# M868tqfp.net
KiCad netlist of a schematic drawn in EAGLE
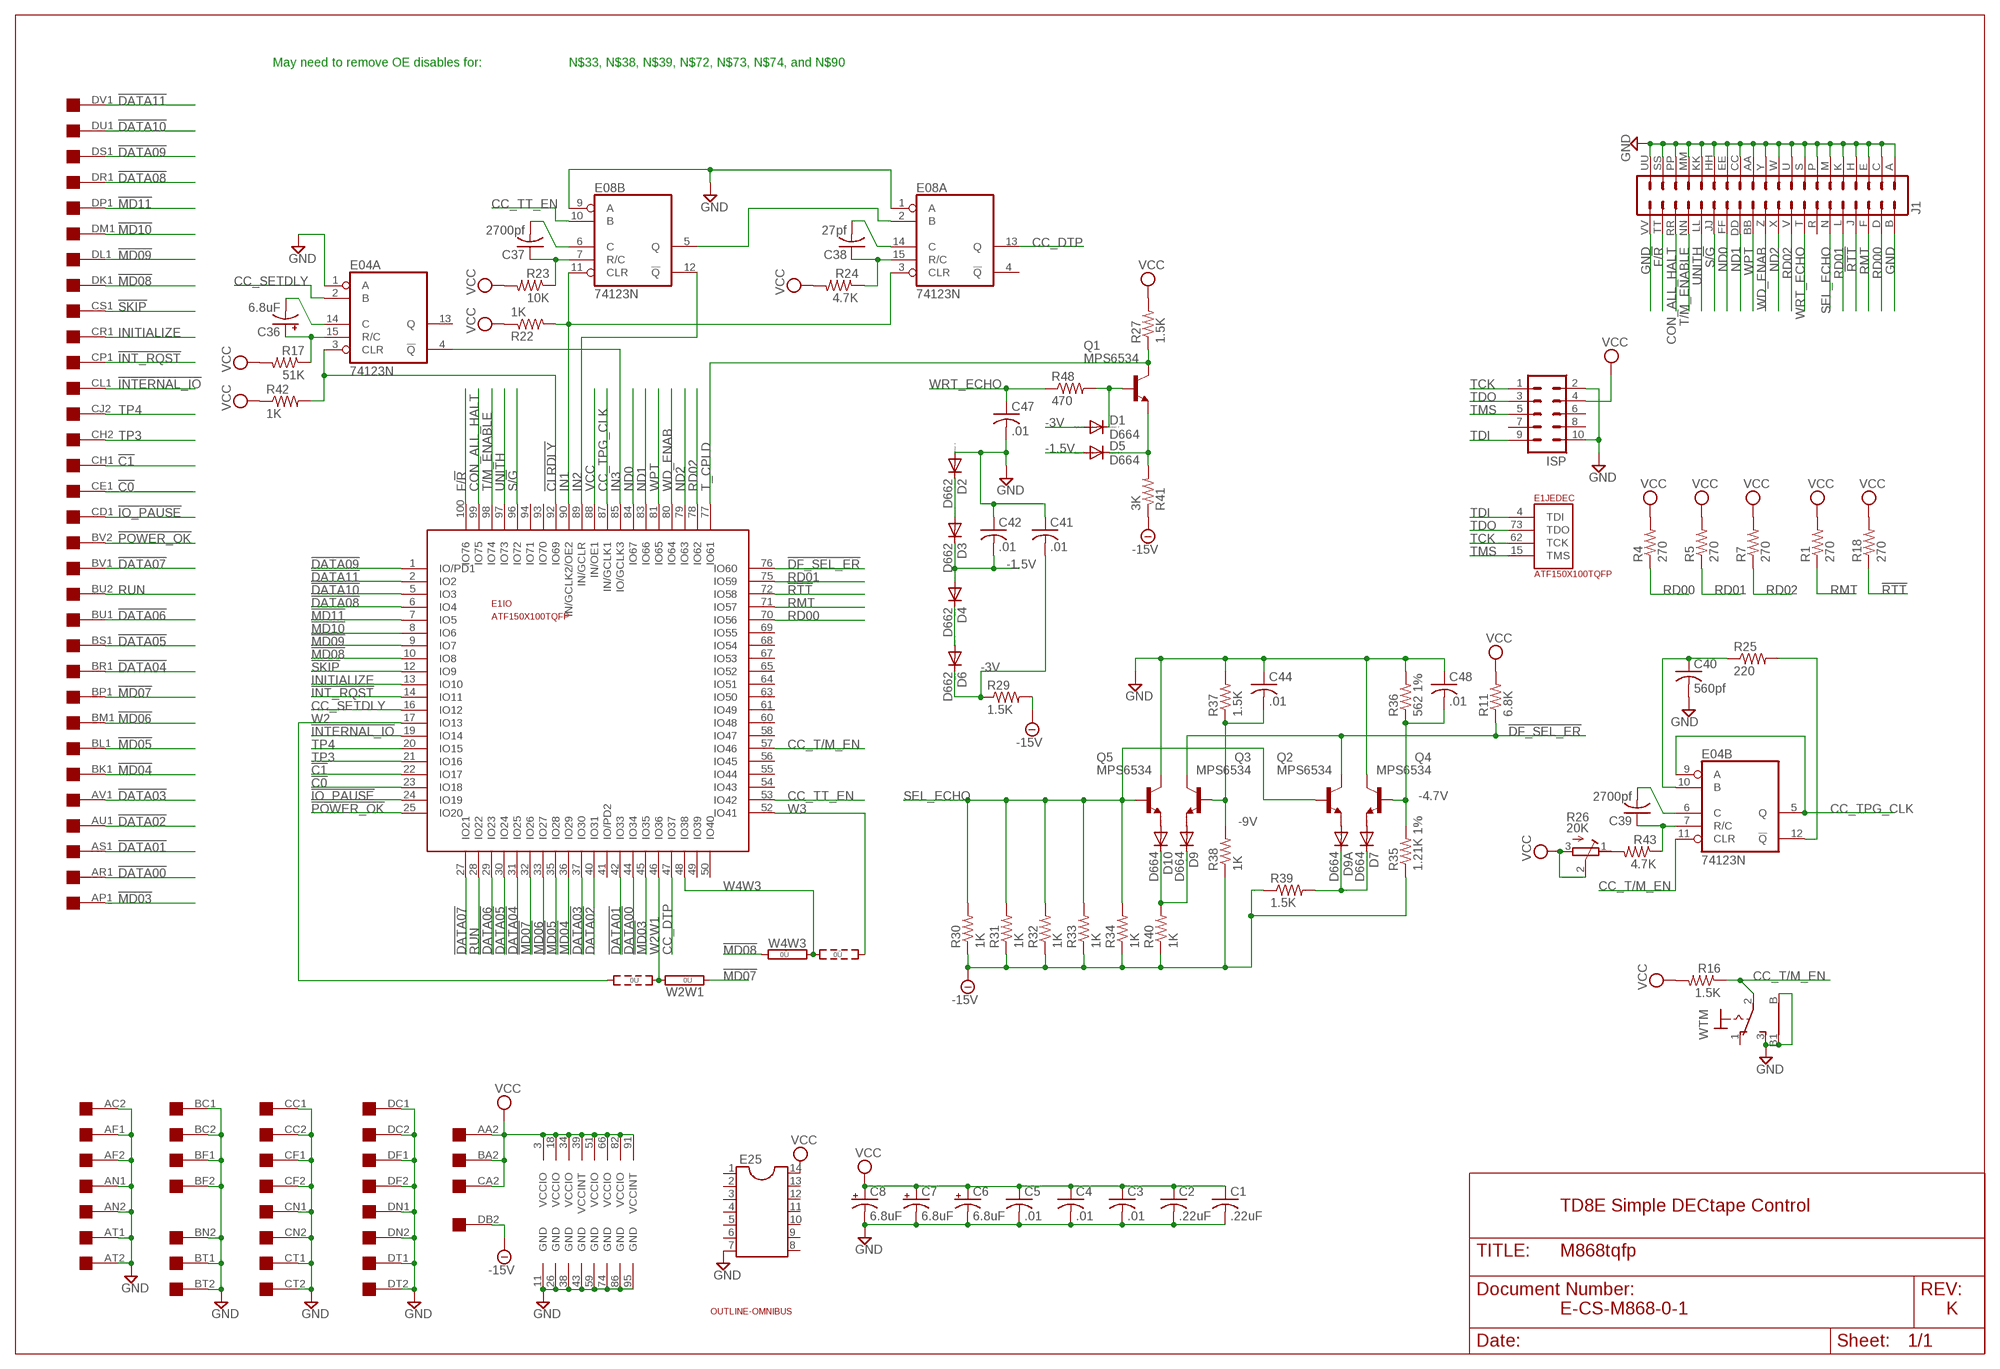
[diagram p0: schematic, sheet 1]

(export (version "E")
  (design (tool "Eeschema 10.0.6"))
  (components
    (comp (ref "C1")
      (value ".22uF")
      (footprint "eagle-import:C050-025X075")
      (libsource (lib "eagle-import") (part "C-US050-025X075"))
    )
    (comp (ref "C2")
      (value ".22uF")
      (footprint "eagle-import:C050-025X075")
      (libsource (lib "eagle-import") (part "C-US050-025X075"))
    )
    (comp (ref "C3")
      (value ".01")
      (footprint "eagle-import:C050-025X075")
      (libsource (lib "eagle-import") (part "C-US050-025X075"))
    )
    (comp (ref "C4")
      (value ".01")
      (footprint "eagle-import:C050-025X075")
      (libsource (lib "eagle-import") (part "C-US050-025X075"))
    )
    (comp (ref "C5")
      (value ".01")
      (footprint "eagle-import:C050-025X075")
      (libsource (lib "eagle-import") (part "C-US050-025X075"))
    )
    (comp (ref "C6")
      (value "6.8uF")
      (footprint "eagle-import:E12-8")
      (libsource (lib "eagle-import") (part "CPOL-USE20-8AXIAL"))
    )
    (comp (ref "C7")
      (value "6.8uF")
      (footprint "eagle-import:E12-8")
      (libsource (lib "eagle-import") (part "CPOL-USE20-8AXIAL"))
    )
    (comp (ref "C8")
      (value "6.8uF")
      (footprint "eagle-import:E12-8")
      (libsource (lib "eagle-import") (part "CPOL-USE20-8AXIAL"))
    )
    (comp (ref "C36")
      (value "6.8uF")
      (footprint "eagle-import:E12-8")
      (libsource (lib "eagle-import") (part "CPOL-USE20-8AXIAL"))
    )
    (comp (ref "C37")
      (value "2700pf")
      (footprint "eagle-import:C102-043X133")
      (libsource (lib "eagle-import") (part "C-US102-043X133"))
    )
    (comp (ref "C38")
      (value "27pf")
      (footprint "eagle-import:C050-025X075")
      (libsource (lib "eagle-import") (part "C-US050-025X075"))
    )
    (comp (ref "C39")
      (value "2700pf")
      (footprint "eagle-import:C102-043X133")
      (libsource (lib "eagle-import") (part "C-US102-043X133"))
    )
    (comp (ref "C40")
      (value "560pf")
      (footprint "eagle-import:C075-032X103")
      (libsource (lib "eagle-import") (part "C-US075-032X103"))
    )
    (comp (ref "C41")
      (value ".01")
      (footprint "eagle-import:C050-025X075")
      (libsource (lib "eagle-import") (part "C-US050-025X075"))
    )
    (comp (ref "C42")
      (value ".01")
      (footprint "eagle-import:C050-025X075")
      (libsource (lib "eagle-import") (part "C-US050-025X075"))
    )
    (comp (ref "C44")
      (value ".01")
      (footprint "eagle-import:C050-025X075")
      (libsource (lib "eagle-import") (part "C-US050-025X075"))
    )
    (comp (ref "C47")
      (value ".01")
      (footprint "eagle-import:C050-025X075")
      (libsource (lib "eagle-import") (part "C-US050-025X075"))
    )
    (comp (ref "C48")
      (value ".01")
      (footprint "eagle-import:C050-025X075")
      (libsource (lib "eagle-import") (part "C-US050-025X075"))
    )
    (comp (ref "D1")
      (value "D664")
      (footprint "eagle-import:DO35-10")
      (libsource (lib "eagle-import") (part "1N4148DO35-10"))
    )
    (comp (ref "D2")
      (value "D662")
      (footprint "eagle-import:DO35-10")
      (libsource (lib "eagle-import") (part "1N4148DO35-10"))
    )
    (comp (ref "D3")
      (value "D662")
      (footprint "eagle-import:DO35-10")
      (libsource (lib "eagle-import") (part "1N4148DO35-10"))
    )
    (comp (ref "D4")
      (value "D662")
      (footprint "eagle-import:DO35-10")
      (libsource (lib "eagle-import") (part "1N4148DO35-10"))
    )
    (comp (ref "D5")
      (value "D664")
      (footprint "eagle-import:DO35-10")
      (libsource (lib "eagle-import") (part "1N4148DO35-10"))
    )
    (comp (ref "D6")
      (value "D662")
      (footprint "eagle-import:DO35-10")
      (libsource (lib "eagle-import") (part "1N4148DO35-10"))
    )
    (comp (ref "D7")
      (value "D664")
      (footprint "eagle-import:DO35-10")
      (libsource (lib "eagle-import") (part "1N4148DO35-10"))
    )
    (comp (ref "D9")
      (value "D664")
      (footprint "eagle-import:DO35-10")
      (libsource (lib "eagle-import") (part "1N4148DO35-10"))
    )
    (comp (ref "D9A")
      (value "D664")
      (footprint "eagle-import:DO35-10")
      (libsource (lib "eagle-import") (part "1N4148DO35-10"))
    )
    (comp (ref "D10")
      (value "D664")
      (footprint "eagle-import:DO35-10")
      (libsource (lib "eagle-import") (part "1N4148DO35-10"))
    )
    (comp (ref "E1")
      (value "ATF150X100TQFP")
      (footprint "eagle-import:TQFP-100")
      (libsource (lib "eagle-import") (part "ATF150X100TQFP"))
    )
    (comp (ref "E04")
      (value "74123N")
      (footprint "eagle-import:DIL16")
      (libsource (lib "eagle-import") (part "74123N"))
    )
    (comp (ref "E08")
      (value "74123N")
      (footprint "eagle-import:DIL16")
      (libsource (lib "eagle-import") (part "74123N"))
    )
    (comp (ref "E25")
      (value "DIL14")
      (footprint "eagle-import:DIL14")
      (libsource (lib "eagle-import") (part "DIL14"))
    )
    (comp (ref "EDGE$3")
      (value "QUAD")
      (footprint "eagle-import:EDGE-CON8")
      (libsource (lib "eagle-import") (part "QUAD"))
    )
    (comp (ref "ISP")
      (value "ML10")
      (footprint "eagle-import:ML10")
      (libsource (lib "eagle-import") (part "ML10"))
    )
    (comp (ref "J1")
      (value "DEC40PINH")
      (footprint "eagle-import:DEC40PINH")
      (libsource (lib "eagle-import") (part "DEC40PINH"))
    )
    (comp (ref "Q1")
      (value "MPS6534")
      (footprint "eagle-import:TO5")
      (libsource (lib "eagle-import") (part "2N2219"))
    )
    (comp (ref "Q2")
      (value "MPS6534")
      (footprint "eagle-import:TO5")
      (libsource (lib "eagle-import") (part "2N2219"))
    )
    (comp (ref "Q3")
      (value "MPS6534")
      (footprint "eagle-import:TO5")
      (libsource (lib "eagle-import") (part "2N2219"))
    )
    (comp (ref "Q4")
      (value "MPS6534")
      (footprint "eagle-import:TO5")
      (libsource (lib "eagle-import") (part "2N2219"))
    )
    (comp (ref "Q5")
      (value "MPS6534")
      (footprint "eagle-import:TO5")
      (libsource (lib "eagle-import") (part "2N2219"))
    )
    (comp (ref "R1")
      (value "270")
      (footprint "eagle-import:0207_10")
      (libsource (lib "eagle-import") (part "R-US_0207/10"))
    )
    (comp (ref "R4")
      (value "270")
      (footprint "eagle-import:0207_10")
      (libsource (lib "eagle-import") (part "R-US_0207/10"))
    )
    (comp (ref "R5")
      (value "270")
      (footprint "eagle-import:0207_10")
      (libsource (lib "eagle-import") (part "R-US_0207/10"))
    )
    (comp (ref "R7")
      (value "270")
      (footprint "eagle-import:0207_10")
      (libsource (lib "eagle-import") (part "R-US_0207/10"))
    )
    (comp (ref "R11")
      (value "6.8K")
      (footprint "eagle-import:0207_10")
      (libsource (lib "eagle-import") (part "R-US_0207/10"))
    )
    (comp (ref "R16")
      (value "1.5K")
      (footprint "eagle-import:0207_10")
      (libsource (lib "eagle-import") (part "R-US_0207/10"))
    )
    (comp (ref "R17")
      (value "51K")
      (footprint "eagle-import:0207_10")
      (libsource (lib "eagle-import") (part "R-US_0207/10"))
    )
    (comp (ref "R18")
      (value "270")
      (footprint "eagle-import:0207_10")
      (libsource (lib "eagle-import") (part "R-US_0207/10"))
    )
    (comp (ref "R22")
      (value "1K")
      (footprint "eagle-import:0207_10")
      (libsource (lib "eagle-import") (part "R-US_0207/10"))
    )
    (comp (ref "R23")
      (value "10K")
      (footprint "eagle-import:0207_10")
      (libsource (lib "eagle-import") (part "R-US_0207/10"))
    )
    (comp (ref "R24")
      (value "4.7K")
      (footprint "eagle-import:0207_10")
      (libsource (lib "eagle-import") (part "R-US_0207/10"))
    )
    (comp (ref "R25")
      (value "220")
      (footprint "eagle-import:0207_10")
      (libsource (lib "eagle-import") (part "R-US_0207/10"))
    )
    (comp (ref "R26")
      (value "20K")
      (footprint "eagle-import:3006Y")
      (libsource (lib "eagle-import") (part "275P"))
    )
    (comp (ref "R27")
      (value "1.5K")
      (footprint "eagle-import:0207_10")
      (libsource (lib "eagle-import") (part "R-US_0207/10"))
    )
    (comp (ref "R29")
      (value "1.5K")
      (footprint "eagle-import:0207_10")
      (libsource (lib "eagle-import") (part "R-US_0207/10"))
    )
    (comp (ref "R30")
      (value "1K")
      (footprint "eagle-import:0207_10")
      (libsource (lib "eagle-import") (part "R-US_0207/10"))
    )
    (comp (ref "R31")
      (value "1K")
      (footprint "eagle-import:0207_10")
      (libsource (lib "eagle-import") (part "R-US_0207/10"))
    )
    (comp (ref "R32")
      (value "1K")
      (footprint "eagle-import:0207_10")
      (libsource (lib "eagle-import") (part "R-US_0207/10"))
    )
    (comp (ref "R33")
      (value "1K")
      (footprint "eagle-import:0207_10")
      (libsource (lib "eagle-import") (part "R-US_0207/10"))
    )
    (comp (ref "R34")
      (value "1K")
      (footprint "eagle-import:0207_10")
      (libsource (lib "eagle-import") (part "R-US_0207/10"))
    )
    (comp (ref "R35")
      (value "1.21K 1%")
      (footprint "eagle-import:0207_15")
      (libsource (lib "eagle-import") (part "R-US_0207/15"))
    )
    (comp (ref "R36")
      (value "562 1%")
      (footprint "eagle-import:0207_15")
      (libsource (lib "eagle-import") (part "R-US_0207/15"))
    )
    (comp (ref "R37")
      (value "1.5K")
      (footprint "eagle-import:0207_10")
      (libsource (lib "eagle-import") (part "R-US_0207/10"))
    )
    (comp (ref "R38")
      (value "1K")
      (footprint "eagle-import:0207_10")
      (libsource (lib "eagle-import") (part "R-US_0207/10"))
    )
    (comp (ref "R39")
      (value "1.5K")
      (footprint "eagle-import:0207_10")
      (libsource (lib "eagle-import") (part "R-US_0207/10"))
    )
    (comp (ref "R40")
      (value "1K")
      (footprint "eagle-import:0207_10")
      (libsource (lib "eagle-import") (part "R-US_0207/10"))
    )
    (comp (ref "R41")
      (value "3K")
      (footprint "eagle-import:0207_10")
      (libsource (lib "eagle-import") (part "R-US_0207/10"))
    )
    (comp (ref "R42")
      (value "1K")
      (footprint "eagle-import:0207_10")
      (libsource (lib "eagle-import") (part "R-US_0207/10"))
    )
    (comp (ref "R43")
      (value "4.7K")
      (footprint "eagle-import:0207_10")
      (libsource (lib "eagle-import") (part "R-US_0207/10"))
    )
    (comp (ref "R48")
      (value "470")
      (footprint "eagle-import:0207_10")
      (libsource (lib "eagle-import") (part "R-US_0207/10"))
    )
    (comp (ref "U$1")
      (value "OUTLINE-OMNIBUS")
      (footprint "eagle-import:OMNIBUS")
      (libsource (lib "eagle-import") (part "OUTLINE-OMNIBUS"))
    )
    (comp (ref "W2W1")
      (value "0R2")
      (footprint "eagle-import:0R2_10")
      (libsource (lib "eagle-import") (part "0R2"))
    )
    (comp (ref "W4W3")
      (value "0R2")
      (footprint "eagle-import:0R2_10")
      (libsource (lib "eagle-import") (part "0R2"))
    )
    (comp (ref "WTM")
      (value "9070-1W")
      (footprint "eagle-import:9070-1W")
      (libsource (lib "eagle-import") (part "9070-1W"))
    )
  )
  (nets
    (net (code "1") (name "-15V") (class "Default")
      (node (ref "EDGE$3") (pin "DB2") (pinfunction "1_DB2") (pintype "bidirectional"))
      (node (ref "R29") (pin "2") (pinfunction "2_2") (pintype "passive"))
      (node (ref "R30") (pin "1") (pinfunction "1_1") (pintype "passive"))
      (node (ref "R31") (pin "1") (pinfunction "1_1") (pintype "passive"))
      (node (ref "R32") (pin "1") (pinfunction "1_1") (pintype "passive"))
      (node (ref "R33") (pin "1") (pinfunction "1_1") (pintype "passive"))
      (node (ref "R34") (pin "1") (pinfunction "1_1") (pintype "passive"))
      (node (ref "R35") (pin "1") (pinfunction "1_1") (pintype "passive"))
      (node (ref "R38") (pin "1") (pinfunction "1_1") (pintype "passive"))
      (node (ref "R39") (pin "1") (pinfunction "1_1") (pintype "passive"))
      (node (ref "R40") (pin "1") (pinfunction "1_1") (pintype "passive"))
      (node (ref "R41") (pin "1") (pinfunction "1_1") (pintype "passive"))
    )
    (net (code "2") (name "/-1.5V") (class "Default")
      (node (ref "C42") (pin "2") (pinfunction "2_2") (pintype "passive"))
      (node (ref "D3") (pin "C") (pinfunction "C_C") (pintype "passive"))
      (node (ref "D4") (pin "A") (pinfunction "A_A") (pintype "passive"))
      (node (ref "D5") (pin "A") (pinfunction "A_A") (pintype "passive"))
    )
    (net (code "3") (name "/-3V") (class "Default")
      (node (ref "C41") (pin "2") (pinfunction "2_2") (pintype "passive"))
      (node (ref "D1") (pin "A") (pinfunction "A_A") (pintype "passive"))
      (node (ref "D6") (pin "C") (pinfunction "C_C") (pintype "passive"))
      (node (ref "R29") (pin "1") (pinfunction "1_1") (pintype "passive"))
    )
    (net (code "4") (name "/-4.7V") (class "Default")
      (node (ref "C48") (pin "2") (pinfunction "2_2") (pintype "passive"))
      (node (ref "Q4") (pin "2") (pinfunction "B_2") (pintype "passive"))
      (node (ref "R35") (pin "2") (pinfunction "2_2") (pintype "passive"))
      (node (ref "R36") (pin "1") (pinfunction "1_1") (pintype "passive"))
    )
    (net (code "5") (name "/-9V") (class "Default")
      (node (ref "C44") (pin "2") (pinfunction "2_2") (pintype "passive"))
      (node (ref "Q3") (pin "2") (pinfunction "B_2") (pintype "passive"))
      (node (ref "R37") (pin "1") (pinfunction "1_1") (pintype "passive"))
      (node (ref "R38") (pin "2") (pinfunction "2_2") (pintype "passive"))
    )
    (net (code "6") (name "/CC_DTP") (class "Default")
      (node (ref "E08") (pin "13") (pinfunction "Q_13") (pintype "output"))
      (node (ref "E1") (pin "47") (pinfunction "IO37_47") (pintype "bidirectional"))
    )
    (net (code "7") (name "/CC_SETDLY") (class "Default")
      (node (ref "E04") (pin "2") (pinfunction "B_2") (pintype "input"))
      (node (ref "E1") (pin "16") (pinfunction "IO12_16") (pintype "bidirectional"))
    )
    (net (code "8") (name "/CC_TPG_CLK") (class "Default")
      (node (ref "E04") (pin "5") (pinfunction "Q_5") (pintype "output"))
      (node (ref "E04") (pin "9") (pinfunction "A_9") (pintype "input"))
      (node (ref "E1") (pin "87") (pinfunction "IN/GCLK1_87") (pintype "input"))
    )
    (net (code "9") (name "/CC_TT_EN") (class "Default")
      (node (ref "E08") (pin "10") (pinfunction "B_10") (pintype "input"))
      (node (ref "E1") (pin "53") (pinfunction "IO42_53") (pintype "bidirectional"))
    )
    (net (code "10") (name "/CC_T{slash}M_EN") (class "Default")
      (node (ref "E04") (pin "11") (pinfunction "CLR_11") (pintype "input"))
      (node (ref "E1") (pin "57") (pinfunction "IO46_57") (pintype "bidirectional"))
      (node (ref "R16") (pin "1") (pinfunction "1_1") (pintype "passive"))
      (node (ref "WTM") (pin "2") (pinfunction "P_2") (pintype "passive"))
    )
    (net (code "11") (name "/CON_ALL_HALT") (class "Default")
      (node (ref "E1") (pin "99") (pinfunction "IO75_99") (pintype "bidirectional"))
      (node (ref "J1") (pin "RR") (pinfunction "36_RR") (pintype "bidirectional"))
    )
    (net (code "12") (name "/F{slash}~{R}") (class "Default")
      (node (ref "E1") (pin "100") (pinfunction "IO76_100") (pintype "bidirectional"))
      (node (ref "J1") (pin "TT") (pinfunction "38_TT") (pintype "bidirectional"))
    )
    (net (code "13") (name "/IN1") (class "Default")
      (node (ref "E08") (pin "11") (pinfunction "CLR_11") (pintype "input"))
      (node (ref "E08") (pin "3") (pinfunction "CLR_3") (pintype "input"))
      (node (ref "E1") (pin "90") (pinfunction "IN/GCLK2/OE2_90") (pintype "input"))
      (node (ref "R22") (pin "2") (pinfunction "2_2") (pintype "passive"))
    )
    (net (code "14") (name "/IN2") (class "Default")
      (node (ref "E08") (pin "12") (pinfunction "~{Q}_12") (pintype "output"))
      (node (ref "E1") (pin "89") (pinfunction "IN/GCLR_89") (pintype "input"))
    )
    (net (code "15") (name "/IN3") (class "Default")
      (node (ref "E04") (pin "4") (pinfunction "~{Q}_4") (pintype "output"))
      (node (ref "E1") (pin "85") (pinfunction "IO/GCLK3_85") (pintype "bidirectional"))
    )
    (net (code "16") (name "/INITIALIZE") (class "Default")
      (node (ref "E1") (pin "13") (pinfunction "IO10_13") (pintype "bidirectional"))
      (node (ref "EDGE$3") (pin "CR1") (pinfunction "1_CR1") (pintype "bidirectional"))
    )
    (net (code "17") (name "/ND0") (class "Default")
      (node (ref "E1") (pin "84") (pinfunction "IO67_84") (pintype "bidirectional"))
      (node (ref "J1") (pin "FF") (pinfunction "28_FF") (pintype "bidirectional"))
    )
    (net (code "18") (name "/ND1") (class "Default")
      (node (ref "E1") (pin "83") (pinfunction "IO66_83") (pintype "bidirectional"))
      (node (ref "J1") (pin "DD") (pinfunction "26_DD") (pintype "bidirectional"))
    )
    (net (code "19") (name "/ND2") (class "Default")
      (node (ref "E1") (pin "79") (pinfunction "IO63_79") (pintype "bidirectional"))
      (node (ref "J1") (pin "X") (pinfunction "20_X") (pintype "bidirectional"))
    )
    (net (code "20") (name "/RD00") (class "Default")
      (node (ref "E1") (pin "70") (pinfunction "IO56_70") (pintype "bidirectional"))
      (node (ref "J1") (pin "D") (pinfunction "4_D") (pintype "bidirectional"))
      (node (ref "R4") (pin "1") (pinfunction "1_1") (pintype "passive"))
    )
    (net (code "21") (name "/RD01") (class "Default")
      (node (ref "E1") (pin "75") (pinfunction "IO59_75") (pintype "bidirectional"))
      (node (ref "J1") (pin "L") (pinfunction "10_L") (pintype "bidirectional"))
      (node (ref "R5") (pin "1") (pinfunction "1_1") (pintype "passive"))
    )
    (net (code "22") (name "/RD02") (class "Default")
      (node (ref "E1") (pin "78") (pinfunction "IO62_78") (pintype "bidirectional"))
      (node (ref "J1") (pin "V") (pinfunction "18_V") (pintype "bidirectional"))
      (node (ref "R7") (pin "1") (pinfunction "1_1") (pintype "passive"))
    )
    (net (code "23") (name "/RMT") (class "Default")
      (node (ref "E1") (pin "71") (pinfunction "IO57_71") (pintype "bidirectional"))
      (node (ref "J1") (pin "F") (pinfunction "6_F") (pintype "bidirectional"))
      (node (ref "R1") (pin "1") (pinfunction "1_1") (pintype "passive"))
    )
    (net (code "24") (name "/RUN") (class "Default")
      (node (ref "E1") (pin "28") (pinfunction "IO22_28") (pintype "bidirectional"))
      (node (ref "EDGE$3") (pin "BU2") (pinfunction "1_BU2") (pintype "bidirectional"))
    )
    (net (code "25") (name "/SEL_ECHO") (class "Default")
      (node (ref "J1") (pin "N") (pinfunction "12_N") (pintype "bidirectional"))
      (node (ref "Q2") (pin "2") (pinfunction "B_2") (pintype "passive"))
      (node (ref "Q5") (pin "2") (pinfunction "B_2") (pintype "passive"))
      (node (ref "R30") (pin "2") (pinfunction "2_2") (pintype "passive"))
      (node (ref "R31") (pin "2") (pinfunction "2_2") (pintype "passive"))
      (node (ref "R32") (pin "2") (pinfunction "2_2") (pintype "passive"))
      (node (ref "R33") (pin "2") (pinfunction "2_2") (pintype "passive"))
      (node (ref "R34") (pin "2") (pinfunction "2_2") (pintype "passive"))
    )
    (net (code "26") (name "/S{slash}~{G}") (class "Default")
      (node (ref "E1") (pin "96") (pinfunction "IO72_96") (pintype "bidirectional"))
      (node (ref "J1") (pin "JJ") (pinfunction "30_JJ") (pintype "bidirectional"))
    )
    (net (code "27") (name "/TCK") (class "Default")
      (node (ref "E1") (pin "62") (pinfunction "TCK_62") (pintype "bidirectional"))
      (node (ref "ISP") (pin "1") (pinfunction "1_1") (pintype "passive"))
    )
    (net (code "28") (name "/TDI") (class "Default")
      (node (ref "E1") (pin "4") (pinfunction "TDI_4") (pintype "bidirectional"))
      (node (ref "ISP") (pin "9") (pinfunction "9_9") (pintype "passive"))
    )
    (net (code "29") (name "/TDO") (class "Default")
      (node (ref "E1") (pin "73") (pinfunction "TDO_73") (pintype "bidirectional"))
      (node (ref "ISP") (pin "3") (pinfunction "3_3") (pintype "passive"))
    )
    (net (code "30") (name "/TMS") (class "Default")
      (node (ref "E1") (pin "15") (pinfunction "TMS_15") (pintype "bidirectional"))
      (node (ref "ISP") (pin "5") (pinfunction "5_5") (pintype "passive"))
    )
    (net (code "31") (name "/TP3") (class "Default")
      (node (ref "E1") (pin "21") (pinfunction "IO16_21") (pintype "bidirectional"))
      (node (ref "EDGE$3") (pin "CH2") (pinfunction "1_CH2") (pintype "bidirectional"))
    )
    (net (code "32") (name "/TP4") (class "Default")
      (node (ref "E1") (pin "20") (pinfunction "IO15_20") (pintype "bidirectional"))
      (node (ref "EDGE$3") (pin "CJ2") (pinfunction "1_CJ2") (pintype "bidirectional"))
    )
    (net (code "33") (name "/T_CPLD") (class "Default")
      (node (ref "E1") (pin "77") (pinfunction "IO61_77") (pintype "bidirectional"))
      (node (ref "Q1") (pin "3") (pinfunction "C_3") (pintype "passive"))
      (node (ref "R27") (pin "1") (pinfunction "1_1") (pintype "passive"))
    )
    (net (code "34") (name "/T{slash}M_ENABLE") (class "Default")
      (node (ref "E1") (pin "98") (pinfunction "IO74_98") (pintype "bidirectional"))
      (node (ref "J1") (pin "NN") (pinfunction "34_NN") (pintype "bidirectional"))
    )
    (net (code "35") (name "/UNITH") (class "Default")
      (node (ref "E1") (pin "97") (pinfunction "IO73_97") (pintype "bidirectional"))
      (node (ref "J1") (pin "LL") (pinfunction "32_LL") (pintype "bidirectional"))
    )
    (net (code "36") (name "/W2") (class "Default")
      (node (ref "E1") (pin "17") (pinfunction "IO13_17") (pintype "bidirectional"))
      (node (ref "W2W1") (pin "3") (pinfunction "3_3") (pintype "passive"))
    )
    (net (code "37") (name "/W2W1") (class "Default")
      (node (ref "E1") (pin "46") (pinfunction "IO36_46") (pintype "bidirectional"))
      (node (ref "W2W1") (pin "2") (pinfunction "2_2") (pintype "passive"))
    )
    (net (code "38") (name "/W3") (class "Default")
      (node (ref "E1") (pin "52") (pinfunction "IO41_52") (pintype "bidirectional"))
      (node (ref "W4W3") (pin "3") (pinfunction "3_3") (pintype "passive"))
    )
    (net (code "39") (name "/W4W3") (class "Default")
      (node (ref "E1") (pin "48") (pinfunction "IO38_48") (pintype "bidirectional"))
      (node (ref "W4W3") (pin "2") (pinfunction "2_2") (pintype "passive"))
    )
    (net (code "40") (name "/WD_ENAB") (class "Default")
      (node (ref "E1") (pin "80") (pinfunction "IO64_80") (pintype "bidirectional"))
      (node (ref "J1") (pin "Z") (pinfunction "22_Z") (pintype "bidirectional"))
    )
    (net (code "41") (name "/WPT") (class "Default")
      (node (ref "E1") (pin "81") (pinfunction "IO65_81") (pintype "bidirectional"))
      (node (ref "J1") (pin "BB") (pinfunction "24_BB") (pintype "bidirectional"))
    )
    (net (code "42") (name "/WRT_ECHO") (class "Default")
      (node (ref "C47") (pin "1") (pinfunction "1_1") (pintype "passive"))
      (node (ref "J1") (pin "T") (pinfunction "16_T") (pintype "bidirectional"))
      (node (ref "R48") (pin "1") (pinfunction "1_1") (pintype "passive"))
    )
    (net (code "43") (name "/~{C0}") (class "Default")
      (node (ref "E1") (pin "23") (pinfunction "IO18_23") (pintype "bidirectional"))
      (node (ref "EDGE$3") (pin "CE1") (pinfunction "1_CE1") (pintype "bidirectional"))
    )
    (net (code "44") (name "/~{C1}") (class "Default")
      (node (ref "E1") (pin "22") (pinfunction "IO17_22") (pintype "bidirectional"))
      (node (ref "EDGE$3") (pin "CH1") (pinfunction "1_CH1") (pintype "bidirectional"))
    )
    (net (code "45") (name "/~{CLRDLY}") (class "Default")
      (node (ref "E04") (pin "3") (pinfunction "CLR_3") (pintype "input"))
      (node (ref "E1") (pin "92") (pinfunction "IO69_92") (pintype "bidirectional"))
      (node (ref "R42") (pin "2") (pinfunction "2_2") (pintype "passive"))
    )
    (net (code "46") (name "/~{DATA00}") (class "Default")
      (node (ref "E1") (pin "44") (pinfunction "IO34_44") (pintype "bidirectional"))
      (node (ref "EDGE$3") (pin "AR1") (pinfunction "1_AR1") (pintype "bidirectional"))
    )
    (net (code "47") (name "/~{DATA01}") (class "Default")
      (node (ref "E1") (pin "42") (pinfunction "IO33_42") (pintype "bidirectional"))
      (node (ref "EDGE$3") (pin "AS1") (pinfunction "1_AS1") (pintype "bidirectional"))
    )
    (net (code "48") (name "/~{DATA02}") (class "Default")
      (node (ref "E1") (pin "40") (pinfunction "IO31_40") (pintype "bidirectional"))
      (node (ref "EDGE$3") (pin "AU1") (pinfunction "1_AU1") (pintype "bidirectional"))
    )
    (net (code "49") (name "/~{DATA03}") (class "Default")
      (node (ref "E1") (pin "37") (pinfunction "IO30_37") (pintype "bidirectional"))
      (node (ref "EDGE$3") (pin "AV1") (pinfunction "1_AV1") (pintype "bidirectional"))
    )
    (net (code "50") (name "/~{DATA04}") (class "Default")
      (node (ref "E1") (pin "31") (pinfunction "IO25_31") (pintype "bidirectional"))
      (node (ref "EDGE$3") (pin "BR1") (pinfunction "1_BR1") (pintype "bidirectional"))
    )
    (net (code "51") (name "/~{DATA05}") (class "Default")
      (node (ref "E1") (pin "30") (pinfunction "IO24_30") (pintype "bidirectional"))
      (node (ref "EDGE$3") (pin "BS1") (pinfunction "1_BS1") (pintype "bidirectional"))
    )
    (net (code "52") (name "/~{DATA06}") (class "Default")
      (node (ref "E1") (pin "29") (pinfunction "IO23_29") (pintype "bidirectional"))
      (node (ref "EDGE$3") (pin "BU1") (pinfunction "1_BU1") (pintype "bidirectional"))
    )
    (net (code "53") (name "/~{DATA07}") (class "Default")
      (node (ref "E1") (pin "27") (pinfunction "IO21_27") (pintype "bidirectional"))
      (node (ref "EDGE$3") (pin "BV1") (pinfunction "1_BV1") (pintype "bidirectional"))
    )
    (net (code "54") (name "/~{DATA08}") (class "Default")
      (node (ref "E1") (pin "6") (pinfunction "IO4_6") (pintype "bidirectional"))
      (node (ref "EDGE$3") (pin "DR1") (pinfunction "1_DR1") (pintype "bidirectional"))
    )
    (net (code "55") (name "/~{DATA09}") (class "Default")
      (node (ref "E1") (pin "1") (pinfunction "IO/PD1_1") (pintype "bidirectional"))
      (node (ref "EDGE$3") (pin "DS1") (pinfunction "1_DS1") (pintype "bidirectional"))
    )
    (net (code "56") (name "/~{DATA10}") (class "Default")
      (node (ref "E1") (pin "5") (pinfunction "IO3_5") (pintype "bidirectional"))
      (node (ref "EDGE$3") (pin "DU1") (pinfunction "1_DU1") (pintype "bidirectional"))
    )
    (net (code "57") (name "/~{DATA11}") (class "Default")
      (node (ref "E1") (pin "2") (pinfunction "IO2_2") (pintype "bidirectional"))
      (node (ref "EDGE$3") (pin "DV1") (pinfunction "1_DV1") (pintype "bidirectional"))
    )
    (net (code "58") (name "/~{DF_SEL_ER}") (class "Default")
      (node (ref "E1") (pin "76") (pinfunction "IO60_76") (pintype "bidirectional"))
      (node (ref "Q2") (pin "3") (pinfunction "C_3") (pintype "passive"))
      (node (ref "Q3") (pin "3") (pinfunction "C_3") (pintype "passive"))
      (node (ref "R11") (pin "1") (pinfunction "1_1") (pintype "passive"))
    )
    (net (code "59") (name "/~{INTERNAL_IO}") (class "Default")
      (node (ref "E1") (pin "19") (pinfunction "IO14_19") (pintype "bidirectional"))
      (node (ref "EDGE$3") (pin "CL1") (pinfunction "1_CL1") (pintype "bidirectional"))
    )
    (net (code "60") (name "/~{INT_RQST}") (class "Default")
      (node (ref "E1") (pin "14") (pinfunction "IO11_14") (pintype "bidirectional"))
      (node (ref "EDGE$3") (pin "CP1") (pinfunction "1_CP1") (pintype "bidirectional"))
    )
    (net (code "61") (name "/~{IO_PAUSE}") (class "Default")
      (node (ref "E1") (pin "24") (pinfunction "IO19_24") (pintype "bidirectional"))
      (node (ref "EDGE$3") (pin "CD1") (pinfunction "1_CD1") (pintype "bidirectional"))
    )
    (net (code "62") (name "/~{MD03}") (class "Default")
      (node (ref "E1") (pin "45") (pinfunction "IO35_45") (pintype "bidirectional"))
      (node (ref "EDGE$3") (pin "AP1") (pinfunction "1_AP1") (pintype "bidirectional"))
    )
    (net (code "63") (name "/~{MD04}") (class "Default")
      (node (ref "E1") (pin "36") (pinfunction "IO29_36") (pintype "bidirectional"))
      (node (ref "EDGE$3") (pin "BK1") (pinfunction "1_BK1") (pintype "bidirectional"))
    )
    (net (code "64") (name "/~{MD05}") (class "Default")
      (node (ref "E1") (pin "35") (pinfunction "IO28_35") (pintype "bidirectional"))
      (node (ref "EDGE$3") (pin "BL1") (pinfunction "1_BL1") (pintype "bidirectional"))
    )
    (net (code "65") (name "/~{MD06}") (class "Default")
      (node (ref "E1") (pin "33") (pinfunction "IO27_33") (pintype "bidirectional"))
      (node (ref "EDGE$3") (pin "BM1") (pinfunction "1_BM1") (pintype "bidirectional"))
    )
    (net (code "66") (name "/~{MD07}") (class "Default")
      (node (ref "E1") (pin "32") (pinfunction "IO26_32") (pintype "bidirectional"))
      (node (ref "EDGE$3") (pin "BP1") (pinfunction "1_BP1") (pintype "bidirectional"))
      (node (ref "W2W1") (pin "1") (pinfunction "1_1") (pintype "passive"))
    )
    (net (code "67") (name "/~{MD08}") (class "Default")
      (node (ref "E1") (pin "10") (pinfunction "IO8_10") (pintype "bidirectional"))
      (node (ref "EDGE$3") (pin "DK1") (pinfunction "1_DK1") (pintype "bidirectional"))
      (node (ref "W4W3") (pin "1") (pinfunction "1_1") (pintype "passive"))
    )
    (net (code "68") (name "/~{MD09}") (class "Default")
      (node (ref "E1") (pin "9") (pinfunction "IO7_9") (pintype "bidirectional"))
      (node (ref "EDGE$3") (pin "DL1") (pinfunction "1_DL1") (pintype "bidirectional"))
    )
    (net (code "69") (name "/~{MD10}") (class "Default")
      (node (ref "E1") (pin "8") (pinfunction "IO6_8") (pintype "bidirectional"))
      (node (ref "EDGE$3") (pin "DM1") (pinfunction "1_DM1") (pintype "bidirectional"))
    )
    (net (code "70") (name "/~{MD11}") (class "Default")
      (node (ref "E1") (pin "7") (pinfunction "IO5_7") (pintype "bidirectional"))
      (node (ref "EDGE$3") (pin "DP1") (pinfunction "1_DP1") (pintype "bidirectional"))
    )
    (net (code "71") (name "/~{POWER_OK}") (class "Default")
      (node (ref "E1") (pin "25") (pinfunction "IO20_25") (pintype "bidirectional"))
      (node (ref "EDGE$3") (pin "BV2") (pinfunction "1_BV2") (pintype "bidirectional"))
    )
    (net (code "72") (name "/~{RTT}") (class "Default")
      (node (ref "E1") (pin "72") (pinfunction "IO58_72") (pintype "bidirectional"))
      (node (ref "J1") (pin "J") (pinfunction "8_J") (pintype "bidirectional"))
      (node (ref "R18") (pin "1") (pinfunction "1_1") (pintype "passive"))
    )
    (net (code "73") (name "/~{SKIP}") (class "Default")
      (node (ref "E1") (pin "12") (pinfunction "IO9_12") (pintype "bidirectional"))
      (node (ref "EDGE$3") (pin "CS1") (pinfunction "1_CS1") (pintype "bidirectional"))
    )
    (net (code "74") (name "GND") (class "Default")
      (node (ref "C1") (pin "2") (pinfunction "2_2") (pintype "passive"))
      (node (ref "C2") (pin "2") (pinfunction "2_2") (pintype "passive"))
      (node (ref "C3") (pin "2") (pinfunction "2_2") (pintype "passive"))
      (node (ref "C4") (pin "2") (pinfunction "2_2") (pintype "passive"))
      (node (ref "C40") (pin "2") (pinfunction "2_2") (pintype "passive"))
      (node (ref "C41") (pin "1") (pinfunction "1_1") (pintype "passive"))
      (node (ref "C42") (pin "1") (pinfunction "1_1") (pintype "passive"))
      (node (ref "C44") (pin "1") (pinfunction "1_1") (pintype "passive"))
      (node (ref "C47") (pin "2") (pinfunction "2_2") (pintype "passive"))
      (node (ref "C48") (pin "1") (pinfunction "1_1") (pintype "passive"))
      (node (ref "C5") (pin "2") (pinfunction "2_2") (pintype "passive"))
      (node (ref "C6") (pin "-") (pinfunction "-_-") (pintype "passive"))
      (node (ref "C7") (pin "-") (pinfunction "-_-") (pintype "passive"))
      (node (ref "C8") (pin "-") (pinfunction "-_-") (pintype "passive"))
      (node (ref "D2") (pin "A") (pinfunction "A_A") (pintype "passive"))
      (node (ref "E04") (pin "1") (pinfunction "A_1") (pintype "input"))
      (node (ref "E08") (pin "1") (pinfunction "A_1") (pintype "input"))
      (node (ref "E08") (pin "9") (pinfunction "A_9") (pintype "input"))
      (node (ref "E1") (pin "11") (pinfunction "GND_11") (pintype "power_in"))
      (node (ref "E1") (pin "26") (pinfunction "GND_26") (pintype "power_in"))
      (node (ref "E1") (pin "38") (pinfunction "GND_38") (pintype "power_in"))
      (node (ref "E1") (pin "43") (pinfunction "GND_43") (pintype "power_in"))
      (node (ref "E1") (pin "59") (pinfunction "GND_59") (pintype "power_in"))
      (node (ref "E1") (pin "74") (pinfunction "GND_74") (pintype "power_in"))
      (node (ref "E1") (pin "86") (pinfunction "GND_86") (pintype "power_in"))
      (node (ref "E1") (pin "95") (pinfunction "GND_95") (pintype "power_in"))
      (node (ref "E25") (pin "7") (pinfunction "7_7") (pintype "passive"))
      (node (ref "EDGE$3") (pin "AC2") (pinfunction "1_AC2") (pintype "bidirectional"))
      (node (ref "EDGE$3") (pin "AF1") (pinfunction "1_AF1") (pintype "bidirectional"))
      (node (ref "EDGE$3") (pin "AF2") (pinfunction "1_AF2") (pintype "bidirectional"))
      (node (ref "EDGE$3") (pin "AN1") (pinfunction "1_AN1") (pintype "bidirectional"))
      (node (ref "EDGE$3") (pin "AN2") (pinfunction "1_AN2") (pintype "bidirectional"))
      (node (ref "EDGE$3") (pin "AT1") (pinfunction "1_AT1") (pintype "bidirectional"))
      (node (ref "EDGE$3") (pin "AT2") (pinfunction "1_AT2") (pintype "bidirectional"))
      (node (ref "EDGE$3") (pin "BC1") (pinfunction "1_BC1") (pintype "bidirectional"))
      (node (ref "EDGE$3") (pin "BC2") (pinfunction "1_BC2") (pintype "bidirectional"))
      (node (ref "EDGE$3") (pin "BF1") (pinfunction "1_BF1") (pintype "bidirectional"))
      (node (ref "EDGE$3") (pin "BF2") (pinfunction "1_BF2") (pintype "bidirectional"))
      (node (ref "EDGE$3") (pin "BN2") (pinfunction "1_BN2") (pintype "bidirectional"))
      (node (ref "EDGE$3") (pin "BT1") (pinfunction "1_BT1") (pintype "bidirectional"))
      (node (ref "EDGE$3") (pin "BT2") (pinfunction "1_BT2") (pintype "bidirectional"))
      (node (ref "EDGE$3") (pin "CC1") (pinfunction "1_CC1") (pintype "bidirectional"))
      (node (ref "EDGE$3") (pin "CC2") (pinfunction "1_CC2") (pintype "bidirectional"))
      (node (ref "EDGE$3") (pin "CF1") (pinfunction "1_CF1") (pintype "bidirectional"))
      (node (ref "EDGE$3") (pin "CF2") (pinfunction "1_CF2") (pintype "bidirectional"))
      (node (ref "EDGE$3") (pin "CN1") (pinfunction "1_CN1") (pintype "bidirectional"))
      (node (ref "EDGE$3") (pin "CN2") (pinfunction "1_CN2") (pintype "bidirectional"))
      (node (ref "EDGE$3") (pin "CT1") (pinfunction "1_CT1") (pintype "bidirectional"))
      (node (ref "EDGE$3") (pin "CT2") (pinfunction "1_CT2") (pintype "bidirectional"))
      (node (ref "EDGE$3") (pin "DC1") (pinfunction "1_DC1") (pintype "bidirectional"))
      (node (ref "EDGE$3") (pin "DC2") (pinfunction "1_DC2") (pintype "bidirectional"))
      (node (ref "EDGE$3") (pin "DF1") (pinfunction "1_DF1") (pintype "bidirectional"))
      (node (ref "EDGE$3") (pin "DF2") (pinfunction "1_DF2") (pintype "bidirectional"))
      (node (ref "EDGE$3") (pin "DN1") (pinfunction "1_DN1") (pintype "bidirectional"))
      (node (ref "EDGE$3") (pin "DN2") (pinfunction "1_DN2") (pintype "bidirectional"))
      (node (ref "EDGE$3") (pin "DT1") (pinfunction "1_DT1") (pintype "bidirectional"))
      (node (ref "EDGE$3") (pin "DT2") (pinfunction "1_DT2") (pintype "bidirectional"))
      (node (ref "ISP") (pin "10") (pinfunction "10_10") (pintype "passive"))
      (node (ref "ISP") (pin "2") (pinfunction "2_2") (pintype "passive"))
      (node (ref "J1") (pin "A") (pinfunction "1_A") (pintype "bidirectional"))
      (node (ref "J1") (pin "AA") (pinfunction "23_AA") (pintype "bidirectional"))
      (node (ref "J1") (pin "B") (pinfunction "2_B") (pintype "bidirectional"))
      (node (ref "J1") (pin "C") (pinfunction "3_C") (pintype "bidirectional"))
      (node (ref "J1") (pin "CC") (pinfunction "25_CC") (pintype "bidirectional"))
      (node (ref "J1") (pin "E") (pinfunction "5_E") (pintype "bidirectional"))
      (node (ref "J1") (pin "EE") (pinfunction "27_EE") (pintype "bidirectional"))
      (node (ref "J1") (pin "H") (pinfunction "7_H") (pintype "bidirectional"))
      (node (ref "J1") (pin "HH") (pinfunction "29_HH") (pintype "bidirectional"))
      (node (ref "J1") (pin "K") (pinfunction "9_K") (pintype "bidirectional"))
      (node (ref "J1") (pin "KK") (pinfunction "31_KK") (pintype "bidirectional"))
      (node (ref "J1") (pin "M") (pinfunction "11_M") (pintype "bidirectional"))
      (node (ref "J1") (pin "MM") (pinfunction "33_MM") (pintype "bidirectional"))
      (node (ref "J1") (pin "P") (pinfunction "13_P") (pintype "bidirectional"))
      (node (ref "J1") (pin "PP") (pinfunction "35_PP") (pintype "bidirectional"))
      (node (ref "J1") (pin "S") (pinfunction "15_S") (pintype "bidirectional"))
      (node (ref "J1") (pin "SS") (pinfunction "37_SS") (pintype "bidirectional"))
      (node (ref "J1") (pin "U") (pinfunction "17_U") (pintype "bidirectional"))
      (node (ref "J1") (pin "UU") (pinfunction "39_UU") (pintype "bidirectional"))
      (node (ref "J1") (pin "VV") (pinfunction "40_VV") (pintype "bidirectional"))
      (node (ref "J1") (pin "W") (pinfunction "19_W") (pintype "bidirectional"))
      (node (ref "J1") (pin "Y") (pinfunction "21_Y") (pintype "bidirectional"))
      (node (ref "Q4") (pin "3") (pinfunction "C_3") (pintype "passive"))
      (node (ref "Q5") (pin "3") (pinfunction "C_3") (pintype "passive"))
      (node (ref "R36") (pin "2") (pinfunction "2_2") (pintype "passive"))
      (node (ref "R37") (pin "2") (pinfunction "2_2") (pintype "passive"))
      (node (ref "WTM") (pin "3") (pinfunction "S_3") (pintype "passive"))
      (node (ref "WTM") (pin "B") (pinfunction "B_B") (pintype "passive"))
      (node (ref "WTM") (pin "B1") (pinfunction "B1_B1") (pintype "passive"))
    )
    (net (code "75") (name "Net-(D2-PadC)") (class "Default")
      (node (ref "D2") (pin "C") (pinfunction "C_C") (pintype "passive"))
      (node (ref "D3") (pin "A") (pinfunction "A_A") (pintype "passive"))
    )
    (net (code "76") (name "Net-(D4-PadC)") (class "Default")
      (node (ref "D4") (pin "C") (pinfunction "C_C") (pintype "passive"))
      (node (ref "D6") (pin "A") (pinfunction "A_A") (pintype "passive"))
    )
    (net (code "77") (name "Net-(D7-PadC)") (class "Default")
      (node (ref "D7") (pin "C") (pinfunction "C_C") (pintype "passive"))
      (node (ref "D9A") (pin "C") (pinfunction "C_C") (pintype "passive"))
      (node (ref "R39") (pin "2") (pinfunction "2_2") (pintype "passive"))
    )
    (net (code "78") (name "Net-(D10-PadC)") (class "Default")
      (node (ref "D10") (pin "C") (pinfunction "C_C") (pintype "passive"))
      (node (ref "D9") (pin "C") (pinfunction "C_C") (pintype "passive"))
      (node (ref "R40") (pin "2") (pinfunction "2_2") (pintype "passive"))
    )
    (net (code "79") (name "Net-(E04A-C)") (class "Default")
      (node (ref "C36") (pin "-") (pinfunction "-_-") (pintype "passive"))
      (node (ref "E04") (pin "14") (pinfunction "C_14") (pintype "input"))
    )
    (net (code "80") (name "Net-(E04A-R{slash}C)") (class "Default")
      (node (ref "C36") (pin "+") (pinfunction "+_+") (pintype "passive"))
      (node (ref "E04") (pin "15") (pinfunction "R/C_15") (pintype "input"))
      (node (ref "R17") (pin "1") (pinfunction "1_1") (pintype "passive"))
    )
    (net (code "81") (name "Net-(E04B-B)") (class "Default")
      (node (ref "C40") (pin "1") (pinfunction "1_1") (pintype "passive"))
      (node (ref "E04") (pin "10") (pinfunction "B_10") (pintype "input"))
      (node (ref "R25") (pin "1") (pinfunction "1_1") (pintype "passive"))
    )
    (net (code "82") (name "Net-(E04B-C)") (class "Default")
      (node (ref "C39") (pin "2") (pinfunction "2_2") (pintype "passive"))
      (node (ref "E04") (pin "6") (pinfunction "C_6") (pintype "input"))
    )
    (net (code "83") (name "Net-(E04B-R{slash}C)") (class "Default")
      (node (ref "C39") (pin "1") (pinfunction "1_1") (pintype "passive"))
      (node (ref "E04") (pin "7") (pinfunction "R/C_7") (pintype "input"))
      (node (ref "R43") (pin "1") (pinfunction "1_1") (pintype "passive"))
    )
    (net (code "84") (name "Net-(E04B-~{Q})") (class "Default")
      (node (ref "E04") (pin "12") (pinfunction "~{Q}_12") (pintype "output"))
      (node (ref "R25") (pin "2") (pinfunction "2_2") (pintype "passive"))
    )
    (net (code "85") (name "Net-(E08A-B)") (class "Default")
      (node (ref "E08") (pin "2") (pinfunction "B_2") (pintype "input"))
      (node (ref "E08") (pin "5") (pinfunction "Q_5") (pintype "output"))
    )
    (net (code "86") (name "Net-(E08A-C)") (class "Default")
      (node (ref "C38") (pin "2") (pinfunction "2_2") (pintype "passive"))
      (node (ref "E08") (pin "14") (pinfunction "C_14") (pintype "input"))
    )
    (net (code "87") (name "Net-(E08A-R{slash}C)") (class "Default")
      (node (ref "C38") (pin "1") (pinfunction "1_1") (pintype "passive"))
      (node (ref "E08") (pin "15") (pinfunction "R/C_15") (pintype "input"))
      (node (ref "R24") (pin "1") (pinfunction "1_1") (pintype "passive"))
    )
    (net (code "88") (name "Net-(E08B-C)") (class "Default")
      (node (ref "C37") (pin "2") (pinfunction "2_2") (pintype "passive"))
      (node (ref "E08") (pin "6") (pinfunction "C_6") (pintype "input"))
    )
    (net (code "89") (name "Net-(E08B-R{slash}C)") (class "Default")
      (node (ref "C37") (pin "1") (pinfunction "1_1") (pintype "passive"))
      (node (ref "E08") (pin "7") (pinfunction "R/C_7") (pintype "input"))
      (node (ref "R23") (pin "1") (pinfunction "1_1") (pintype "passive"))
    )
    (net (code "90") (name "Net-(Q1-B)") (class "Default")
      (node (ref "D1") (pin "C") (pinfunction "C_C") (pintype "passive"))
      (node (ref "Q1") (pin "2") (pinfunction "B_2") (pintype "passive"))
      (node (ref "R48") (pin "2") (pinfunction "2_2") (pintype "passive"))
    )
    (net (code "91") (name "Net-(Q1-E)") (class "Default")
      (node (ref "D5") (pin "C") (pinfunction "C_C") (pintype "passive"))
      (node (ref "Q1") (pin "1") (pinfunction "E_1") (pintype "passive"))
      (node (ref "R41") (pin "2") (pinfunction "2_2") (pintype "passive"))
    )
    (net (code "92") (name "Net-(Q2-E)") (class "Default")
      (node (ref "D9A") (pin "A") (pinfunction "A_A") (pintype "passive"))
      (node (ref "Q2") (pin "1") (pinfunction "E_1") (pintype "passive"))
    )
    (net (code "93") (name "Net-(Q3-E)") (class "Default")
      (node (ref "D9") (pin "A") (pinfunction "A_A") (pintype "passive"))
      (node (ref "Q3") (pin "1") (pinfunction "E_1") (pintype "passive"))
    )
    (net (code "94") (name "Net-(Q4-E)") (class "Default")
      (node (ref "D7") (pin "A") (pinfunction "A_A") (pintype "passive"))
      (node (ref "Q4") (pin "1") (pinfunction "E_1") (pintype "passive"))
    )
    (net (code "95") (name "Net-(Q5-E)") (class "Default")
      (node (ref "D10") (pin "A") (pinfunction "A_A") (pintype "passive"))
      (node (ref "Q5") (pin "1") (pinfunction "E_1") (pintype "passive"))
    )
    (net (code "96") (name "Net-(R26-A)") (class "Default")
      (node (ref "R26") (pin "1") (pinfunction "A_1") (pintype "passive"))
      (node (ref "R43") (pin "2") (pinfunction "2_2") (pintype "passive"))
    )
    (net (code "97") (name "VCC") (class "Default")
      (node (ref "C1") (pin "1") (pinfunction "1_1") (pintype "passive"))
      (node (ref "C2") (pin "1") (pinfunction "1_1") (pintype "passive"))
      (node (ref "C3") (pin "1") (pinfunction "1_1") (pintype "passive"))
      (node (ref "C4") (pin "1") (pinfunction "1_1") (pintype "passive"))
      (node (ref "C5") (pin "1") (pinfunction "1_1") (pintype "passive"))
      (node (ref "C6") (pin "+") (pinfunction "+_+") (pintype "passive"))
      (node (ref "C7") (pin "+") (pinfunction "+_+") (pintype "passive"))
      (node (ref "C8") (pin "+") (pinfunction "+_+") (pintype "passive"))
      (node (ref "E1") (pin "18") (pinfunction "VCCIO_18") (pintype "power_in"))
      (node (ref "E1") (pin "3") (pinfunction "VCCIO_3") (pintype "power_in"))
      (node (ref "E1") (pin "34") (pinfunction "VCCIO_34") (pintype "power_in"))
      (node (ref "E1") (pin "39") (pinfunction "VCCINT_39") (pintype "power_in"))
      (node (ref "E1") (pin "51") (pinfunction "VCCIO_51") (pintype "power_in"))
      (node (ref "E1") (pin "66") (pinfunction "VCCIO_66") (pintype "power_in"))
      (node (ref "E1") (pin "82") (pinfunction "VCCIO_82") (pintype "power_in"))
      (node (ref "E1") (pin "88") (pinfunction "IN/OE1_88") (pintype "input"))
      (node (ref "E1") (pin "91") (pinfunction "VCCINT_91") (pintype "power_in"))
      (node (ref "E25") (pin "14") (pinfunction "14_14") (pintype "passive"))
      (node (ref "EDGE$3") (pin "AA2") (pinfunction "1_AA2") (pintype "bidirectional"))
      (node (ref "EDGE$3") (pin "BA2") (pinfunction "1_BA2") (pintype "bidirectional"))
      (node (ref "EDGE$3") (pin "CA2") (pinfunction "1_CA2") (pintype "bidirectional"))
      (node (ref "ISP") (pin "4") (pinfunction "4_4") (pintype "passive"))
      (node (ref "R1") (pin "2") (pinfunction "2_2") (pintype "passive"))
      (node (ref "R11") (pin "2") (pinfunction "2_2") (pintype "passive"))
      (node (ref "R16") (pin "2") (pinfunction "2_2") (pintype "passive"))
      (node (ref "R17") (pin "2") (pinfunction "2_2") (pintype "passive"))
      (node (ref "R18") (pin "2") (pinfunction "2_2") (pintype "passive"))
      (node (ref "R22") (pin "1") (pinfunction "1_1") (pintype "passive"))
      (node (ref "R23") (pin "2") (pinfunction "2_2") (pintype "passive"))
      (node (ref "R24") (pin "2") (pinfunction "2_2") (pintype "passive"))
      (node (ref "R26") (pin "2") (pinfunction "S_2") (pintype "passive"))
      (node (ref "R26") (pin "3") (pinfunction "E_3") (pintype "passive"))
      (node (ref "R27") (pin "2") (pinfunction "2_2") (pintype "passive"))
      (node (ref "R4") (pin "2") (pinfunction "2_2") (pintype "passive"))
      (node (ref "R42") (pin "1") (pinfunction "1_1") (pintype "passive"))
      (node (ref "R5") (pin "2") (pinfunction "2_2") (pintype "passive"))
      (node (ref "R7") (pin "2") (pinfunction "2_2") (pintype "passive"))
    )
    (net (code "98") (name "unconnected-(E1Q-IO39-Pad49)") (class "Default")
      (node (ref "E1") (pin "49") (pinfunction "IO39_49") (pintype "bidirectional"))
    )
    (net (code "99") (name "unconnected-(E1Q-IO40-Pad50)") (class "Default")
      (node (ref "E1") (pin "50") (pinfunction "IO40_50") (pintype "bidirectional"))
    )
    (net (code "100") (name "unconnected-(E1Q-IO43-Pad54)") (class "Default")
      (node (ref "E1") (pin "54") (pinfunction "IO43_54") (pintype "bidirectional"))
    )
    (net (code "101") (name "unconnected-(E1Q-IO44-Pad55)") (class "Default")
      (node (ref "E1") (pin "55") (pinfunction "IO44_55") (pintype "bidirectional"))
    )
    (net (code "102") (name "unconnected-(E1Q-IO45-Pad56)") (class "Default")
      (node (ref "E1") (pin "56") (pinfunction "IO45_56") (pintype "bidirectional"))
    )
    (net (code "103") (name "unconnected-(E1Q-IO47-Pad58)") (class "Default")
      (node (ref "E1") (pin "58") (pinfunction "IO47_58") (pintype "bidirectional"))
    )
    (net (code "104") (name "unconnected-(E1Q-IO48-Pad60)") (class "Default")
      (node (ref "E1") (pin "60") (pinfunction "IO48_60") (pintype "bidirectional"))
    )
    (net (code "105") (name "unconnected-(E1Q-IO49-Pad61)") (class "Default")
      (node (ref "E1") (pin "61") (pinfunction "IO49_61") (pintype "bidirectional"))
    )
    (net (code "106") (name "unconnected-(E1Q-IO50-Pad63)") (class "Default")
      (node (ref "E1") (pin "63") (pinfunction "IO50_63") (pintype "bidirectional"))
    )
    (net (code "107") (name "unconnected-(E1Q-IO51-Pad64)") (class "Default")
      (node (ref "E1") (pin "64") (pinfunction "IO51_64") (pintype "bidirectional"))
    )
    (net (code "108") (name "unconnected-(E1Q-IO52-Pad65)") (class "Default")
      (node (ref "E1") (pin "65") (pinfunction "IO52_65") (pintype "bidirectional"))
    )
    (net (code "109") (name "unconnected-(E1Q-IO53-Pad67)") (class "Default")
      (node (ref "E1") (pin "67") (pinfunction "IO53_67") (pintype "bidirectional"))
    )
    (net (code "110") (name "unconnected-(E1Q-IO54-Pad68)") (class "Default")
      (node (ref "E1") (pin "68") (pinfunction "IO54_68") (pintype "bidirectional"))
    )
    (net (code "111") (name "unconnected-(E1Q-IO55-Pad69)") (class "Default")
      (node (ref "E1") (pin "69") (pinfunction "IO55_69") (pintype "bidirectional"))
    )
    (net (code "112") (name "unconnected-(E1Q-IO70-Pad93)") (class "Default")
      (node (ref "E1") (pin "93") (pinfunction "IO70_93") (pintype "bidirectional"))
    )
    (net (code "113") (name "unconnected-(E1Q-IO71-Pad94)") (class "Default")
      (node (ref "E1") (pin "94") (pinfunction "IO71_94") (pintype "bidirectional"))
    )
    (net (code "114") (name "unconnected-(E1Q-IO{slash}PD2-Pad41)") (class "Default")
      (node (ref "E1") (pin "41") (pinfunction "IO/PD2_41") (pintype "bidirectional"))
    )
    (net (code "115") (name "unconnected-(E04A-Q-Pad13)") (class "Default")
      (node (ref "E04") (pin "13") (pinfunction "Q_13") (pintype "output"))
    )
    (net (code "116") (name "unconnected-(E08A-~{Q}-Pad4)") (class "Default")
      (node (ref "E08") (pin "4") (pinfunction "~{Q}_4") (pintype "output"))
    )
    (net (code "117") (name "unconnected-(E25-Pad1)") (class "Default")
      (node (ref "E25") (pin "1") (pinfunction "1_1") (pintype "passive"))
    )
    (net (code "118") (name "unconnected-(E25-Pad2)") (class "Default")
      (node (ref "E25") (pin "2") (pinfunction "2_2") (pintype "passive"))
    )
    (net (code "119") (name "unconnected-(E25-Pad3)") (class "Default")
      (node (ref "E25") (pin "3") (pinfunction "3_3") (pintype "passive"))
    )
    (net (code "120") (name "unconnected-(E25-Pad4)") (class "Default")
      (node (ref "E25") (pin "4") (pinfunction "4_4") (pintype "passive"))
    )
    (net (code "121") (name "unconnected-(E25-Pad5)") (class "Default")
      (node (ref "E25") (pin "5") (pinfunction "5_5") (pintype "passive"))
    )
    (net (code "122") (name "unconnected-(E25-Pad6)") (class "Default")
      (node (ref "E25") (pin "6") (pinfunction "6_6") (pintype "passive"))
    )
    (net (code "123") (name "unconnected-(E25-Pad8)") (class "Default")
      (node (ref "E25") (pin "8") (pinfunction "8_8") (pintype "passive"))
    )
    (net (code "124") (name "unconnected-(E25-Pad9)") (class "Default")
      (node (ref "E25") (pin "9") (pinfunction "9_9") (pintype "passive"))
    )
    (net (code "125") (name "unconnected-(E25-Pad10)") (class "Default")
      (node (ref "E25") (pin "10") (pinfunction "10_10") (pintype "passive"))
    )
    (net (code "126") (name "unconnected-(E25-Pad11)") (class "Default")
      (node (ref "E25") (pin "11") (pinfunction "11_11") (pintype "passive"))
    )
    (net (code "127") (name "unconnected-(E25-Pad12)") (class "Default")
      (node (ref "E25") (pin "12") (pinfunction "12_12") (pintype "passive"))
    )
    (net (code "128") (name "unconnected-(E25-Pad13)") (class "Default")
      (node (ref "E25") (pin "13") (pinfunction "13_13") (pintype "passive"))
    )
    (net (code "129") (name "unconnected-(ISP-Pad6)") (class "Default")
      (node (ref "ISP") (pin "6") (pinfunction "6_6") (pintype "passive"))
    )
    (net (code "130") (name "unconnected-(ISP-Pad7)") (class "Default")
      (node (ref "ISP") (pin "7") (pinfunction "7_7") (pintype "passive"))
    )
    (net (code "131") (name "unconnected-(ISP-Pad8)") (class "Default")
      (node (ref "ISP") (pin "8") (pinfunction "8_8") (pintype "passive"))
    )
    (net (code "132") (name "unconnected-(J1-14-PadR)") (class "Default")
      (node (ref "J1") (pin "R") (pinfunction "14_R") (pintype "bidirectional"))
    )
    (net (code "133") (name "unconnected-(WTM-O-Pad1)") (class "Default")
      (node (ref "WTM") (pin "1") (pinfunction "O_1") (pintype "passive"))
    )
  )
)
